# MX.net
KiCad netlist of a schematic drawn in Altium Designer
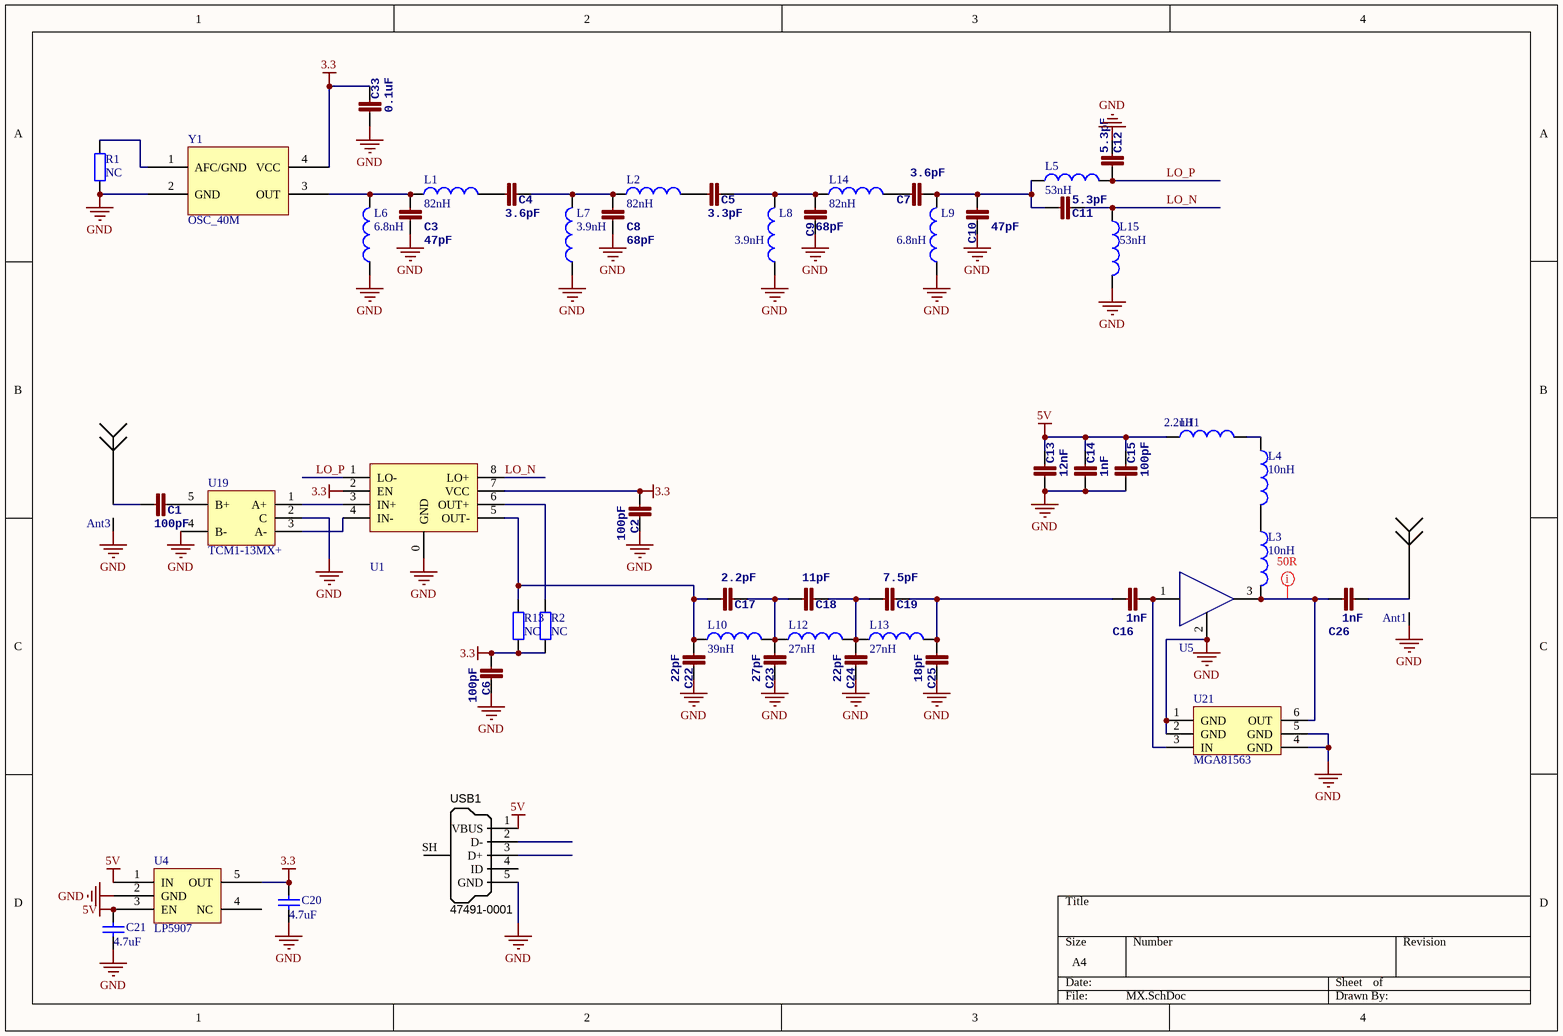
[diagram p0: MX.SchDoc]

(export (version "E")
  (design (tool "Eeschema 10.0.6"))
  (components
    (comp (ref "Ant1") (value "Antenna") (footprint "BK5811:SMA") (libsource (lib "F4SDR") (part "Antenna")))
    (comp (ref "Ant3") (value "Antenna") (footprint "BK5811:SMA") (libsource (lib "F4SDR") (part "Antenna")))
    (comp (ref "C1")
      (value "100pF")
      (footprint "0402")
      (description "<b>Capacitor</b>\nStandard 0603 ceramic capacitor, and 0.1\" leaded capacitor.")
      (fields (field (name "PARTNO") "CC0402ZRY5V7BB104"))
      (libsource (lib "pixhawk2") (part "CAP0402-CAP"))
    )
    (comp (ref "C2")
      (value "100pF")
      (footprint "0402")
      (description "<b>Capacitor</b>\nStandard 0603 ceramic capacitor, and 0.1\" leaded capacitor.")
      (fields (field (name "PARTNO") "CC0402ZRY5V7BB104"))
      (libsource (lib "") (part "CAP0402-CAP_2"))
    )
    (comp (ref "C3")
      (value "47pF")
      (footprint "0402")
      (description "<b>Capacitor</b>\nStandard 0603 ceramic capacitor, and 0.1\" leaded capacitor.")
      (fields (field (name "PARTNO") "CC0402ZRY5V7BB104"))
      (libsource (lib "") (part "CAP0402-CAP_2"))
    )
    (comp (ref "C4")
      (value "3.6pF")
      (footprint "0402")
      (description "<b>Capacitor</b>\nStandard 0603 ceramic capacitor, and 0.1\" leaded capacitor.")
      (fields (field (name "PARTNO") "CC0402ZRY5V7BB104"))
      (libsource (lib "pixhawk2") (part "CAP0402-CAP"))
    )
    (comp (ref "C5")
      (value "3.3pF")
      (footprint "0402")
      (description "<b>Capacitor</b>\nStandard 0603 ceramic capacitor, and 0.1\" leaded capacitor.")
      (fields (field (name "PARTNO") "CC0402ZRY5V7BB104"))
      (libsource (lib "pixhawk2") (part "CAP0402-CAP"))
    )
    (comp (ref "C6")
      (value "100pF")
      (footprint "0402")
      (description "<b>Capacitor</b>\nStandard 0603 ceramic capacitor, and 0.1\" leaded capacitor.")
      (fields (field (name "PARTNO") "CC0402ZRY5V7BB104"))
      (libsource (lib "") (part "CAP0402-CAP_2"))
    )
    (comp (ref "C7")
      (value "3.6pF")
      (footprint "0402")
      (description "<b>Capacitor</b>\nStandard 0603 ceramic capacitor, and 0.1\" leaded capacitor.")
      (fields (field (name "PARTNO") "CC0402ZRY5V7BB104"))
      (libsource (lib "pixhawk2") (part "CAP0402-CAP"))
    )
    (comp (ref "C8")
      (value "68pF")
      (footprint "0402")
      (description "<b>Capacitor</b>\nStandard 0603 ceramic capacitor, and 0.1\" leaded capacitor.")
      (fields (field (name "PARTNO") "CC0402ZRY5V7BB104"))
      (libsource (lib "") (part "CAP0402-CAP_2"))
    )
    (comp (ref "C9")
      (value "68pF")
      (footprint "0402")
      (description "<b>Capacitor</b>\nStandard 0603 ceramic capacitor, and 0.1\" leaded capacitor.")
      (fields (field (name "PARTNO") "CC0402ZRY5V7BB104"))
      (libsource (lib "") (part "CAP0402-CAP_2"))
    )
    (comp (ref "C10")
      (value "47pF")
      (footprint "0402")
      (description "<b>Capacitor</b>\nStandard 0603 ceramic capacitor, and 0.1\" leaded capacitor.")
      (fields (field (name "PARTNO") "CC0402ZRY5V7BB104"))
      (libsource (lib "") (part "CAP0402-CAP_2"))
    )
    (comp (ref "C11")
      (value "5.3pF")
      (footprint "0402")
      (description "<b>Capacitor</b>\nStandard 0603 ceramic capacitor, and 0.1\" leaded capacitor.")
      (fields (field (name "PARTNO") "CC0402ZRY5V7BB104"))
      (libsource (lib "pixhawk2") (part "CAP0402-CAP"))
    )
    (comp (ref "C12")
      (value "5.3pF")
      (footprint "0402")
      (description "<b>Capacitor</b>\nStandard 0603 ceramic capacitor, and 0.1\" leaded capacitor.")
      (fields (field (name "PARTNO") "CC0402ZRY5V7BB104"))
      (libsource (lib "") (part "CAP0402-CAP_1"))
    )
    (comp (ref "C13")
      (value "12nF")
      (footprint "0805")
      (description "<b>Capacitor</b>\nStandard 0603 ceramic capacitor, and 0.1\" leaded capacitor.")
      (fields (field (name "PARTNO") "CC0402ZRY5V7BB104"))
      (libsource (lib "") (part "CAP0402-CAP_1"))
    )
    (comp (ref "C14")
      (value "1nF")
      (footprint "0402")
      (description "<b>Capacitor</b>\nStandard 0603 ceramic capacitor, and 0.1\" leaded capacitor.")
      (fields (field (name "PARTNO") "CC0402ZRY5V7BB104"))
      (libsource (lib "") (part "CAP0402-CAP_1"))
    )
    (comp (ref "C15")
      (value "100pF")
      (footprint "0402")
      (description "<b>Capacitor</b>\nStandard 0603 ceramic capacitor, and 0.1\" leaded capacitor.")
      (fields (field (name "PARTNO") "CC0402ZRY5V7BB104"))
      (libsource (lib "") (part "CAP0402-CAP_1"))
    )
    (comp (ref "C16")
      (value "1nF")
      (footprint "0402")
      (description "<b>Capacitor</b>\nStandard 0603 ceramic capacitor, and 0.1\" leaded capacitor.")
      (fields (field (name "PARTNO") "CC0402ZRY5V7BB104"))
      (libsource (lib "pixhawk2") (part "CAP0402-CAP"))
    )
    (comp (ref "C17")
      (value "2.2pF")
      (footprint "0402")
      (description "<b>Capacitor</b>\nStandard 0603 ceramic capacitor, and 0.1\" leaded capacitor.")
      (fields (field (name "PARTNO") "CC0402ZRY5V7BB104"))
      (libsource (lib "pixhawk2") (part "CAP0402-CAP"))
    )
    (comp (ref "C18")
      (value "11pF")
      (footprint "0402")
      (description "<b>Capacitor</b>\nStandard 0603 ceramic capacitor, and 0.1\" leaded capacitor.")
      (fields (field (name "PARTNO") "CC0402ZRY5V7BB104"))
      (libsource (lib "pixhawk2") (part "CAP0402-CAP"))
    )
    (comp (ref "C19")
      (value "7.5pF")
      (footprint "0402")
      (description "<b>Capacitor</b>\nStandard 0603 ceramic capacitor, and 0.1\" leaded capacitor.")
      (fields (field (name "PARTNO") "CC0402ZRY5V7BB104"))
      (libsource (lib "pixhawk2") (part "CAP0402-CAP"))
    )
    (comp (ref "C20")
      (value "4.7uF")
      (footprint "0603L")
      (description "Capacitor")
      (fields (field (name "PUBLISHER") "Altium Limited"))
      (libsource (lib "RTC6705") (part "Cap"))
    )
    (comp (ref "C21")
      (value "4.7uF")
      (footprint "0603L")
      (description "Capacitor")
      (fields (field (name "PUBLISHER") "Altium Limited"))
      (libsource (lib "RTC6705") (part "Cap"))
    )
    (comp (ref "C22")
      (value "22pF")
      (footprint "0402")
      (description "<b>Capacitor</b>\nStandard 0603 ceramic capacitor, and 0.1\" leaded capacitor.")
      (fields (field (name "PARTNO") "CC0402ZRY5V7BB104"))
      (libsource (lib "") (part "CAP0402-CAP_2"))
    )
    (comp (ref "C23")
      (value "27pF")
      (footprint "0402")
      (description "<b>Capacitor</b>\nStandard 0603 ceramic capacitor, and 0.1\" leaded capacitor.")
      (fields (field (name "PARTNO") "CC0402ZRY5V7BB104"))
      (libsource (lib "") (part "CAP0402-CAP_2"))
    )
    (comp (ref "C24")
      (value "22pF")
      (footprint "0402")
      (description "<b>Capacitor</b>\nStandard 0603 ceramic capacitor, and 0.1\" leaded capacitor.")
      (fields (field (name "PARTNO") "CC0402ZRY5V7BB104"))
      (libsource (lib "") (part "CAP0402-CAP_2"))
    )
    (comp (ref "C25")
      (value "18pF")
      (footprint "0402")
      (description "<b>Capacitor</b>\nStandard 0603 ceramic capacitor, and 0.1\" leaded capacitor.")
      (fields (field (name "PARTNO") "CC0402ZRY5V7BB104"))
      (libsource (lib "") (part "CAP0402-CAP_2"))
    )
    (comp (ref "C26")
      (value "1nF")
      (footprint "0402")
      (description "<b>Capacitor</b>\nStandard 0603 ceramic capacitor, and 0.1\" leaded capacitor.")
      (fields (field (name "PARTNO") "CC0402ZRY5V7BB104"))
      (libsource (lib "pixhawk2") (part "CAP0402-CAP"))
    )
    (comp (ref "C33")
      (value "0.1uF")
      (footprint "0402")
      (description "<b>Capacitor</b>\nStandard 0603 ceramic capacitor, and 0.1\" leaded capacitor.")
      (fields (field (name "PARTNO") "CC0402ZRY5V7BB104"))
      (libsource (lib "") (part "CAP0402-CAP_1"))
    )
    (comp (ref "L1")
      (value "82nH")
      (footprint "0402")
      (description "Inductor")
      (fields (field (name "PUBLISHER") "Altium Limited"))
      (libsource (lib "Miscellaneous Devices") (part "Inductor"))
    )
    (comp (ref "L2")
      (value "82nH")
      (footprint "0402")
      (description "Inductor")
      (fields (field (name "PUBLISHER") "Altium Limited"))
      (libsource (lib "Miscellaneous Devices") (part "Inductor"))
    )
    (comp (ref "L3")
      (value "10nH")
      (footprint "0402")
      (description "Inductor")
      (fields (field (name "PUBLISHER") "Altium Limited"))
      (libsource (lib "Miscellaneous Devices") (part "Inductor"))
    )
    (comp (ref "L4")
      (value "10nH")
      (footprint "0603")
      (description "Inductor")
      (fields (field (name "PUBLISHER") "Altium Limited"))
      (libsource (lib "Miscellaneous Devices") (part "Inductor"))
    )
    (comp (ref "L5")
      (value "53nH")
      (footprint "0402")
      (description "Inductor")
      (fields (field (name "PUBLISHER") "Altium Limited"))
      (libsource (lib "Miscellaneous Devices") (part "Inductor"))
    )
    (comp (ref "L6")
      (value "6.8nH")
      (footprint "0402")
      (description "Inductor")
      (fields (field (name "PUBLISHER") "Altium Limited"))
      (libsource (lib "Miscellaneous Devices") (part "Inductor"))
    )
    (comp (ref "L7")
      (value "3.9nH")
      (footprint "0402")
      (description "Inductor")
      (fields (field (name "PUBLISHER") "Altium Limited"))
      (libsource (lib "Miscellaneous Devices") (part "Inductor"))
    )
    (comp (ref "L8")
      (value "3.9nH")
      (footprint "0402")
      (description "Inductor")
      (fields (field (name "PUBLISHER") "Altium Limited"))
      (libsource (lib "Miscellaneous Devices") (part "Inductor"))
    )
    (comp (ref "L9")
      (value "6.8nH")
      (footprint "0402")
      (description "Inductor")
      (fields (field (name "PUBLISHER") "Altium Limited"))
      (libsource (lib "Miscellaneous Devices") (part "Inductor"))
    )
    (comp (ref "L10")
      (value "39nH")
      (footprint "0402")
      (description "Inductor")
      (fields (field (name "PUBLISHER") "Altium Limited"))
      (libsource (lib "Miscellaneous Devices") (part "Inductor"))
    )
    (comp (ref "L11")
      (value "2.2uH")
      (footprint "L4015")
      (description "Inductor")
      (fields (field (name "PUBLISHER") "Altium Limited"))
      (libsource (lib "Miscellaneous Devices") (part "Inductor"))
    )
    (comp (ref "L12")
      (value "27nH")
      (footprint "0402")
      (description "Inductor")
      (fields (field (name "PUBLISHER") "Altium Limited"))
      (libsource (lib "Miscellaneous Devices") (part "Inductor"))
    )
    (comp (ref "L13")
      (value "27nH")
      (footprint "0402")
      (description "Inductor")
      (fields (field (name "PUBLISHER") "Altium Limited"))
      (libsource (lib "Miscellaneous Devices") (part "Inductor"))
    )
    (comp (ref "L14")
      (value "82nH")
      (footprint "0402")
      (description "Inductor")
      (fields (field (name "PUBLISHER") "Altium Limited"))
      (libsource (lib "Miscellaneous Devices") (part "Inductor"))
    )
    (comp (ref "L15")
      (value "53nH")
      (footprint "0402")
      (description "Inductor")
      (fields (field (name "PUBLISHER") "Altium Limited"))
      (libsource (lib "Miscellaneous Devices") (part "Inductor"))
    )
    (comp (ref "R1")
      (value "NC")
      (footprint "0402")
      (description "Resistor")
      (fields (field (name "PUBLISHER") "Altium Limited"))
      (libsource (lib "Miscellaneous Devices") (part "Res2"))
    )
    (comp (ref "R2")
      (value "NC")
      (footprint "0402")
      (description "Resistor")
      (fields (field (name "PUBLISHER") "Altium Limited"))
      (libsource (lib "Miscellaneous Devices") (part "Res2"))
    )
    (comp (ref "R13")
      (value "NC")
      (footprint "0402")
      (description "Resistor")
      (fields (field (name "PUBLISHER") "Altium Limited"))
      (libsource (lib "Miscellaneous Devices") (part "Res2"))
    )
    (comp (ref "U1") (value "LT5560") (footprint "LT5560") (libsource (lib "F4SDR") (part "LT5560")))
    (comp (ref "U4") (value "LP5907") (footprint "SOT23-5") (libsource (lib "RTC6705") (part "LP5907")))
    (comp (ref "U5") (value "AMP-SOT89") (footprint "SOT-89") (libsource (lib "F4SDR") (part "AMP-SOT89")))
    (comp (ref "U19")
      (value "TCM1-13MX+")
      (footprint "TCM-13M+")
      (libsource (lib "F4SDR") (part "TCM1-1-13M+"))
    )
    (comp (ref "U21") (value "MGA81563") (footprint "SC-70-6") (libsource (lib "F4SDR") (part "MGA81563")))
    (comp (ref "USB1")
      (value "USB Micro Type B")
      (footprint "MICRO-YZX")
      (description "Connector SMD USB Micro Type B middle mount")
      (fields (field (name "MANUFACTURER PART NUMBER 1") "47491-0001"))
      (libsource (lib "PBL - Connectors") (part "USB_Micro_TypeB"))
    )
    (comp (ref "Y1") (value "OSC_40M") (footprint "TXC_7Q") (libsource (lib "F4SDR") (part "OSC_40M")))
  )
  (nets
    (net (code "1") (name "/LO_N") (class "Default")
      (node (ref "C11") (pin "2") (pinfunction "2_2") (pintype "passive"))
      (node (ref "L15") (pin "1") (pinfunction "1_1") (pintype "passive"))
      (node (ref "U1") (pin "8") (pinfunction "LO+_8") (pintype "passive"))
    )
    (net (code "2") (name "/LO_P") (class "Default")
      (node (ref "C12") (pin "1") (pinfunction "1_1") (pintype "passive"))
      (node (ref "L5") (pin "2") (pinfunction "2_2") (pintype "passive"))
      (node (ref "U1") (pin "1") (pinfunction "LO-_1") (pintype "passive"))
    )
    (net (code "3") (name "3.3") (class "Default")
      (node (ref "C2") (pin "1") (pinfunction "1_1") (pintype "passive"))
      (node (ref "C20") (pin "2") (pinfunction "2_2") (pintype "passive"))
      (node (ref "C33") (pin "2") (pinfunction "2_2") (pintype "passive"))
      (node (ref "C6") (pin "1") (pinfunction "1_1") (pintype "passive"))
      (node (ref "R13") (pin "2") (pinfunction "2_2") (pintype "passive"))
      (node (ref "R2") (pin "2") (pinfunction "2_2") (pintype "passive"))
      (node (ref "U1") (pin "2") (pinfunction "EN_2") (pintype "passive"))
      (node (ref "U1") (pin "7") (pinfunction "VCC_7") (pintype "passive"))
      (node (ref "U4") (pin "5") (pinfunction "OUT_5") (pintype "passive"))
      (node (ref "Y1") (pin "4") (pinfunction "VCC_4") (pintype "passive"))
    )
    (net (code "4") (name "5V") (class "Default")
      (node (ref "C13") (pin "2") (pinfunction "2_2") (pintype "passive"))
      (node (ref "C14") (pin "2") (pinfunction "2_2") (pintype "passive"))
      (node (ref "C15") (pin "2") (pinfunction "2_2") (pintype "passive"))
      (node (ref "C21") (pin "2") (pinfunction "2_2") (pintype "passive"))
      (node (ref "L11") (pin "1") (pinfunction "1_1") (pintype "passive"))
      (node (ref "U4") (pin "1") (pinfunction "IN_1") (pintype "passive"))
      (node (ref "U4") (pin "3") (pinfunction "EN_3") (pintype "passive"))
      (node (ref "USB1") (pin "1") (pinfunction "VBUS_1") (pintype "passive"))
    )
    (net (code "5") (name "GND") (class "Default")
      (node (ref "Ant1") (pin "GND") (pinfunction "G_GND") (pintype "passive"))
      (node (ref "Ant3") (pin "GND") (pinfunction "G_GND") (pintype "passive"))
      (node (ref "C10") (pin "2") (pinfunction "2_2") (pintype "passive"))
      (node (ref "C12") (pin "2") (pinfunction "2_2") (pintype "passive"))
      (node (ref "C13") (pin "1") (pinfunction "1_1") (pintype "passive"))
      (node (ref "C14") (pin "1") (pinfunction "1_1") (pintype "passive"))
      (node (ref "C15") (pin "1") (pinfunction "1_1") (pintype "passive"))
      (node (ref "C2") (pin "2") (pinfunction "2_2") (pintype "passive"))
      (node (ref "C20") (pin "1") (pinfunction "1_1") (pintype "passive"))
      (node (ref "C21") (pin "1") (pinfunction "1_1") (pintype "passive"))
      (node (ref "C22") (pin "2") (pinfunction "2_2") (pintype "passive"))
      (node (ref "C23") (pin "2") (pinfunction "2_2") (pintype "passive"))
      (node (ref "C24") (pin "2") (pinfunction "2_2") (pintype "passive"))
      (node (ref "C25") (pin "2") (pinfunction "2_2") (pintype "passive"))
      (node (ref "C3") (pin "2") (pinfunction "2_2") (pintype "passive"))
      (node (ref "C33") (pin "1") (pinfunction "1_1") (pintype "passive"))
      (node (ref "C6") (pin "2") (pinfunction "2_2") (pintype "passive"))
      (node (ref "C8") (pin "2") (pinfunction "2_2") (pintype "passive"))
      (node (ref "C9") (pin "2") (pinfunction "2_2") (pintype "passive"))
      (node (ref "L15") (pin "2") (pinfunction "2_2") (pintype "passive"))
      (node (ref "L6") (pin "1") (pinfunction "1_1") (pintype "passive"))
      (node (ref "L7") (pin "1") (pinfunction "1_1") (pintype "passive"))
      (node (ref "L8") (pin "1") (pinfunction "1_1") (pintype "passive"))
      (node (ref "L9") (pin "1") (pinfunction "1_1") (pintype "passive"))
      (node (ref "R1") (pin "2") (pinfunction "2_2") (pintype "passive"))
      (node (ref "U1") (pin "0") (pinfunction "GND_0") (pintype "passive"))
      (node (ref "U19") (pin "2") (pinfunction "C_2") (pintype "passive"))
      (node (ref "U19") (pin "4") (pinfunction "B-_4") (pintype "passive"))
      (node (ref "U21") (pin "1") (pinfunction "GND_1") (pintype "passive"))
      (node (ref "U21") (pin "2") (pinfunction "GND_2") (pintype "passive"))
      (node (ref "U21") (pin "4") (pinfunction "GND_4") (pintype "passive"))
      (node (ref "U21") (pin "5") (pinfunction "GND_5") (pintype "passive"))
      (node (ref "U4") (pin "2") (pinfunction "GND_2") (pintype "passive"))
      (node (ref "U5") (pin "2") (pinfunction "2_2") (pintype "passive"))
      (node (ref "USB1") (pin "5") (pinfunction "GND_5") (pintype "passive"))
      (node (ref "Y1") (pin "2") (pinfunction "GND_2") (pintype "passive"))
    )
    (net (code "6") (name "Net-(Ant1-Pad1)") (class "Default")
      (node (ref "Ant1") (pin "1") (pinfunction "1_1") (pintype "passive"))
      (node (ref "C26") (pin "2") (pinfunction "2_2") (pintype "passive"))
    )
    (net (code "7") (name "Net-(Ant3-Pad1)") (class "Default")
      (node (ref "Ant3") (pin "1") (pinfunction "1_1") (pintype "passive"))
      (node (ref "C1") (pin "1") (pinfunction "1_1") (pintype "passive"))
    )
    (net (code "8") (name "Net-(C4-Pad1)") (class "Default")
      (node (ref "C4") (pin "1") (pinfunction "1_1") (pintype "passive"))
      (node (ref "L1") (pin "2") (pinfunction "2_2") (pintype "passive"))
    )
    (net (code "9") (name "Net-(C4-Pad2)") (class "Default")
      (node (ref "C4") (pin "2") (pinfunction "2_2") (pintype "passive"))
      (node (ref "C8") (pin "1") (pinfunction "1_1") (pintype "passive"))
      (node (ref "L2") (pin "1") (pinfunction "1_1") (pintype "passive"))
      (node (ref "L7") (pin "2") (pinfunction "2_2") (pintype "passive"))
    )
    (net (code "10") (name "Net-(C5-Pad1)") (class "Default")
      (node (ref "C5") (pin "1") (pinfunction "1_1") (pintype "passive"))
      (node (ref "L2") (pin "2") (pinfunction "2_2") (pintype "passive"))
    )
    (net (code "11") (name "Net-(C5-Pad2)") (class "Default")
      (node (ref "C5") (pin "2") (pinfunction "2_2") (pintype "passive"))
      (node (ref "C9") (pin "1") (pinfunction "1_1") (pintype "passive"))
      (node (ref "L14") (pin "1") (pinfunction "1_1") (pintype "passive"))
      (node (ref "L8") (pin "2") (pinfunction "2_2") (pintype "passive"))
    )
    (net (code "12") (name "Net-(C7-Pad1)") (class "Default")
      (node (ref "C7") (pin "1") (pinfunction "1_1") (pintype "passive"))
      (node (ref "L14") (pin "2") (pinfunction "2_2") (pintype "passive"))
    )
    (net (code "13") (name "Net-(C10-Pad1)") (class "Default")
      (node (ref "C10") (pin "1") (pinfunction "1_1") (pintype "passive"))
      (node (ref "C11") (pin "1") (pinfunction "1_1") (pintype "passive"))
      (node (ref "C7") (pin "2") (pinfunction "2_2") (pintype "passive"))
      (node (ref "L5") (pin "1") (pinfunction "1_1") (pintype "passive"))
      (node (ref "L9") (pin "2") (pinfunction "2_2") (pintype "passive"))
    )
    (net (code "14") (name "Net-(C16-Pad1)") (class "Default")
      (node (ref "C16") (pin "1") (pinfunction "1_1") (pintype "passive"))
      (node (ref "C19") (pin "2") (pinfunction "2_2") (pintype "passive"))
      (node (ref "C25") (pin "1") (pinfunction "1_1") (pintype "passive"))
      (node (ref "L13") (pin "2") (pinfunction "2_2") (pintype "passive"))
    )
    (net (code "15") (name "Net-(C17-Pad2)") (class "Default")
      (node (ref "C17") (pin "2") (pinfunction "2_2") (pintype "passive"))
      (node (ref "C18") (pin "1") (pinfunction "1_1") (pintype "passive"))
      (node (ref "C23") (pin "1") (pinfunction "1_1") (pintype "passive"))
      (node (ref "L10") (pin "2") (pinfunction "2_2") (pintype "passive"))
      (node (ref "L12") (pin "1") (pinfunction "1_1") (pintype "passive"))
    )
    (net (code "16") (name "Net-(C18-Pad2)") (class "Default")
      (node (ref "C18") (pin "2") (pinfunction "2_2") (pintype "passive"))
      (node (ref "C19") (pin "1") (pinfunction "1_1") (pintype "passive"))
      (node (ref "C24") (pin "1") (pinfunction "1_1") (pintype "passive"))
      (node (ref "L12") (pin "2") (pinfunction "2_2") (pintype "passive"))
      (node (ref "L13") (pin "1") (pinfunction "1_1") (pintype "passive"))
    )
    (net (code "17") (name "Net-(L3-Pad1)") (class "Default")
      (node (ref "L3") (pin "1") (pinfunction "1_1") (pintype "passive"))
      (node (ref "L4") (pin "2") (pinfunction "2_2") (pintype "passive"))
    )
    (net (code "18") (name "Net-(L11-Pad2)") (class "Default")
      (node (ref "L11") (pin "2") (pinfunction "2_2") (pintype "passive"))
      (node (ref "L4") (pin "1") (pinfunction "1_1") (pintype "passive"))
    )
    (net (code "19") (name "Net-(U1-IN+)") (class "Default")
      (node (ref "U1") (pin "3") (pinfunction "IN+_3") (pintype "passive"))
      (node (ref "U19") (pin "1") (pinfunction "A+_1") (pintype "passive"))
    )
    (net (code "20") (name "Net-(U1-IN-)") (class "Default")
      (node (ref "U1") (pin "4") (pinfunction "IN-_4") (pintype "passive"))
      (node (ref "U19") (pin "3") (pinfunction "A-_3") (pintype "passive"))
    )
    (net (code "21") (name "Net-(U1-OUT+)") (class "Default")
      (node (ref "R2") (pin "1") (pinfunction "1_1") (pintype "passive"))
      (node (ref "U1") (pin "6") (pinfunction "OUT+_6") (pintype "passive"))
    )
    (net (code "22") (name "Net-(U1-OUT-)") (class "Default")
      (node (ref "C17") (pin "1") (pinfunction "1_1") (pintype "passive"))
      (node (ref "C22") (pin "1") (pinfunction "1_1") (pintype "passive"))
      (node (ref "L10") (pin "1") (pinfunction "1_1") (pintype "passive"))
      (node (ref "R13") (pin "1") (pinfunction "1_1") (pintype "passive"))
      (node (ref "U1") (pin "5") (pinfunction "OUT-_5") (pintype "passive"))
    )
    (net (code "23") (name "Net-(U19-B+)") (class "Default")
      (node (ref "C1") (pin "2") (pinfunction "2_2") (pintype "passive"))
      (node (ref "U19") (pin "5") (pinfunction "B+_5") (pintype "passive"))
    )
    (net (code "24") (name "Net-(U21-IN)") (class "Default")
      (node (ref "C16") (pin "2") (pinfunction "2_2") (pintype "passive"))
      (node (ref "U21") (pin "3") (pinfunction "IN_3") (pintype "passive"))
      (node (ref "U5") (pin "1") (pinfunction "1_1") (pintype "passive"))
    )
    (net (code "25") (name "Net-(U21-OUT)") (class "Default")
      (node (ref "C26") (pin "1") (pinfunction "1_1") (pintype "passive"))
      (node (ref "L3") (pin "2") (pinfunction "2_2") (pintype "passive"))
      (node (ref "U21") (pin "6") (pinfunction "OUT_6") (pintype "passive"))
      (node (ref "U5") (pin "3") (pinfunction "3_3") (pintype "passive"))
    )
    (net (code "26") (name "Net-(Y1-AFC{slash}GND)") (class "Default")
      (node (ref "R1") (pin "1") (pinfunction "1_1") (pintype "passive"))
      (node (ref "Y1") (pin "1") (pinfunction "AFC/GND_1") (pintype "passive"))
    )
    (net (code "27") (name "Net-(Y1-OUT)") (class "Default")
      (node (ref "C3") (pin "1") (pinfunction "1_1") (pintype "passive"))
      (node (ref "L1") (pin "1") (pinfunction "1_1") (pintype "passive"))
      (node (ref "L6") (pin "2") (pinfunction "2_2") (pintype "passive"))
      (node (ref "Y1") (pin "3") (pinfunction "OUT_3") (pintype "passive"))
    )
    (net (code "28") (name "unconnected-(U4-NC-Pad4)") (class "Default")
      (node (ref "U4") (pin "4") (pinfunction "NC_4") (pintype "passive"))
    )
    (net (code "29") (name "unconnected-(USB1-D+-Pad3)") (class "Default")
      (node (ref "USB1") (pin "3") (pinfunction "D+_3") (pintype "passive"))
    )
    (net (code "30") (name "unconnected-(USB1-D--Pad2)") (class "Default")
      (node (ref "USB1") (pin "2") (pinfunction "D-_2") (pintype "passive"))
    )
    (net (code "31") (name "unconnected-(USB1-ID-Pad4)") (class "Default")
      (node (ref "USB1") (pin "4") (pinfunction "ID_4") (pintype "passive"))
    )
    (net (code "32") (name "unconnected-(USB1-Shell-PadSH)") (class "Default")
      (node (ref "USB1") (pin "SH") (pinfunction "Shell_SH") (pintype "passive"))
    )
  )
)
